# Uhr3r4_1.net
KiCad netlist of a schematic drawn in EAGLE
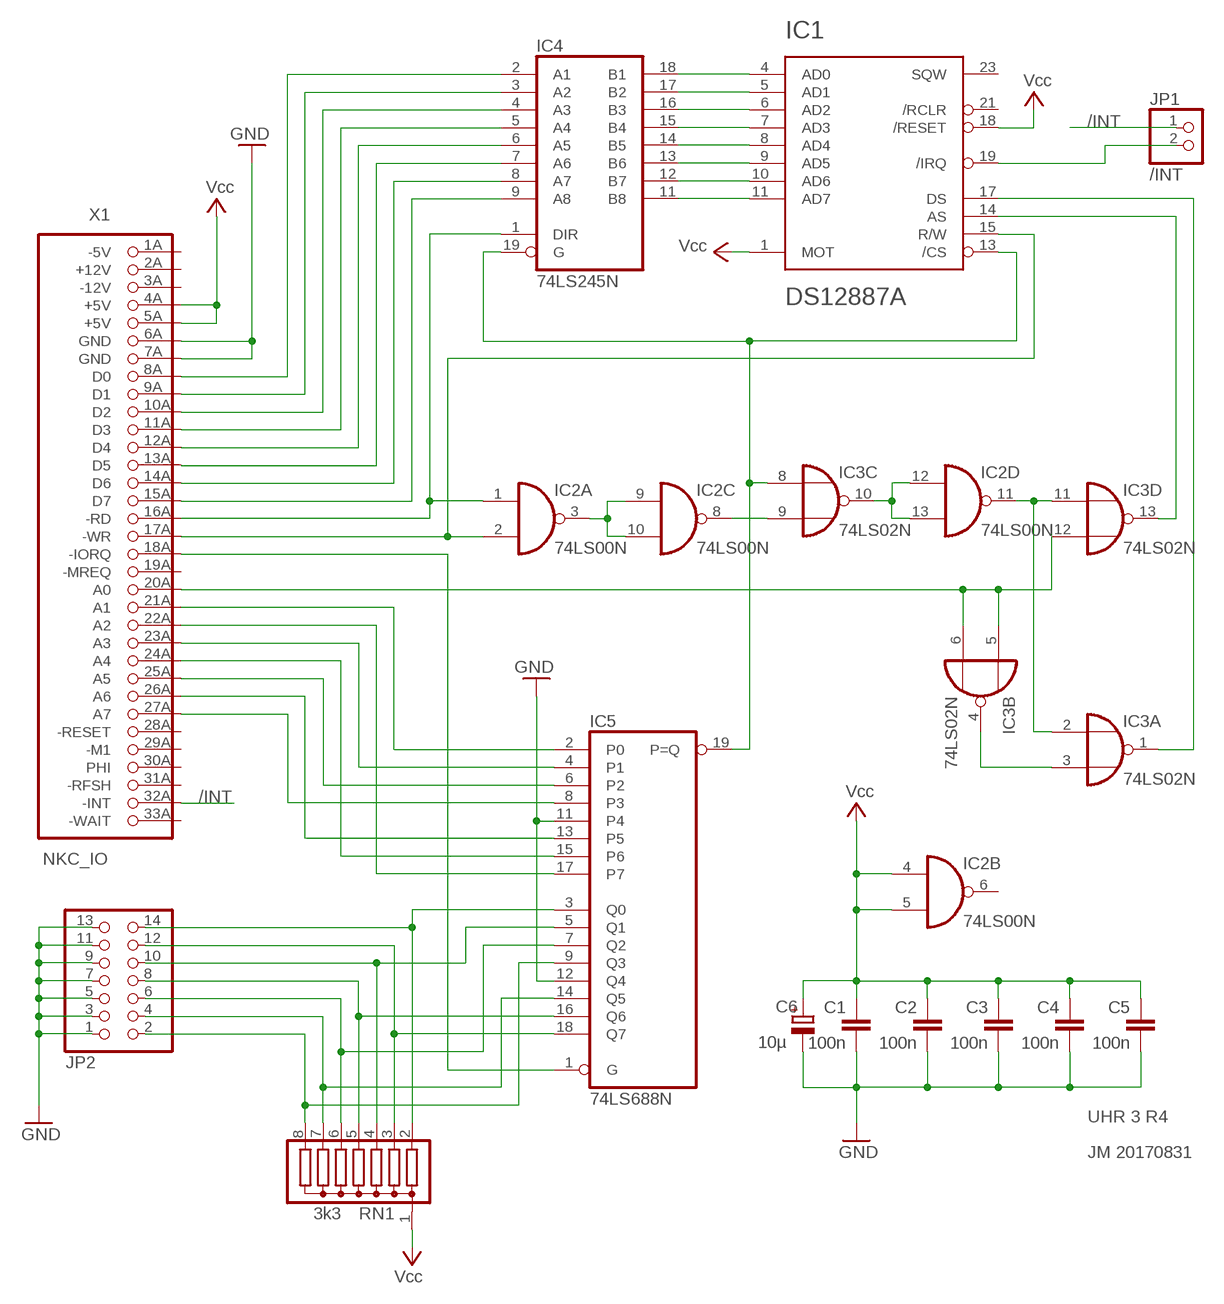
[diagram p0: schematic, sheet 1]

(export (version "E")
  (design (tool "Eeschema 10.0.6"))
  (components
    (comp (ref "C1")
      (value "100n")
      (footprint "eagle-import:C025-025X050")
      (libsource (lib "eagle-import") (part "C-EU025-025X050"))
    )
    (comp (ref "C2")
      (value "100n")
      (footprint "eagle-import:C025-025X050")
      (libsource (lib "eagle-import") (part "C-EU025-025X050"))
    )
    (comp (ref "C3")
      (value "100n")
      (footprint "eagle-import:C025-025X050")
      (libsource (lib "eagle-import") (part "C-EU025-025X050"))
    )
    (comp (ref "C4")
      (value "100n")
      (footprint "eagle-import:C025-025X050")
      (libsource (lib "eagle-import") (part "C-EU025-025X050"))
    )
    (comp (ref "C5")
      (value "100n")
      (footprint "eagle-import:C025-025X050")
      (libsource (lib "eagle-import") (part "C-EU025-025X050"))
    )
    (comp (ref "C6")
      (value "10µ")
      (footprint "eagle-import:E2,5-5")
      (libsource (lib "eagle-import") (part "CPOL-EUE2.5-5"))
    )
    (comp (ref "IC1")
      (value "DS12887A")
      (footprint "eagle-import:DIL24-6_DS")
      (libsource (lib "eagle-import") (part "DS12887A"))
    )
    (comp (ref "IC2")
      (value "74LS00N")
      (footprint "eagle-import:DIL14")
      (libsource (lib "eagle-import") (part "7400NLS"))
    )
    (comp (ref "IC3")
      (value "74LS02N")
      (footprint "eagle-import:DIL14")
      (libsource (lib "eagle-import") (part "7402NLS"))
    )
    (comp (ref "IC4")
      (value "74LS245N")
      (footprint "eagle-import:DIL20")
      (libsource (lib "eagle-import") (part "74245NLS"))
    )
    (comp (ref "IC5")
      (value "74LS688N")
      (footprint "eagle-import:DIL20")
      (libsource (lib "eagle-import") (part "74688NLS"))
    )
    (comp (ref "JP1")
      (value "/INT")
      (footprint "eagle-import:1X02")
      (libsource (lib "eagle-import") (part "PINHD-1X2"))
    )
    (comp (ref "JP2")
      (value "PINHD-2X7")
      (footprint "eagle-import:2X07")
      (libsource (lib "eagle-import") (part "PINHD-2X7"))
    )
    (comp (ref "RN1")
      (value "3k3")
      (footprint "eagle-import:SIL8")
      (libsource (lib "eagle-import") (part "G07R"))
    )
    (comp (ref "X1")
      (value "NKC_IO")
      (footprint "eagle-import:1X33_90_PCB")
      (libsource (lib "eagle-import") (part "NKC_IO"))
    )
  )
  (nets
    (net (code "1") (name "/+12V") (class "Default")
      (node (ref "X1") (pin "2A") (pinfunction "+12V_2A") (pintype "power_in"))
    )
    (net (code "2") (name "/-5V") (class "Default")
      (node (ref "X1") (pin "1A") (pinfunction "-5V_1A") (pintype "power_in"))
    )
    (net (code "3") (name "/-12V") (class "Default")
      (node (ref "X1") (pin "3A") (pinfunction "-12V_3A") (pintype "power_in"))
    )
    (net (code "4") (name "/{slash}INT") (class "Default")
      (node (ref "JP1") (pin "1") (pinfunction "1_1") (pintype "passive"))
      (node (ref "X1") (pin "32A") (pinfunction "-INT_32A") (pintype "bidirectional"))
    )
    (net (code "5") (name "GND") (class "Default")
      (node (ref "C1") (pin "1") (pinfunction "1_1") (pintype "passive"))
      (node (ref "C2") (pin "1") (pinfunction "1_1") (pintype "passive"))
      (node (ref "C3") (pin "1") (pinfunction "1_1") (pintype "passive"))
      (node (ref "C4") (pin "1") (pinfunction "1_1") (pintype "passive"))
      (node (ref "C5") (pin "1") (pinfunction "1_1") (pintype "passive"))
      (node (ref "C6") (pin "-") (pinfunction "-_-") (pintype "passive"))
      (node (ref "IC5") (pin "11") (pinfunction "P4_11") (pintype "input"))
      (node (ref "IC5") (pin "12") (pinfunction "Q4_12") (pintype "input"))
      (node (ref "JP2") (pin "1") (pinfunction "1_1") (pintype "passive"))
      (node (ref "JP2") (pin "11") (pinfunction "11_11") (pintype "passive"))
      (node (ref "JP2") (pin "13") (pinfunction "13_13") (pintype "passive"))
      (node (ref "JP2") (pin "3") (pinfunction "3_3") (pintype "passive"))
      (node (ref "JP2") (pin "5") (pinfunction "5_5") (pintype "passive"))
      (node (ref "JP2") (pin "7") (pinfunction "7_7") (pintype "passive"))
      (node (ref "JP2") (pin "9") (pinfunction "9_9") (pintype "passive"))
      (node (ref "X1") (pin "6A") (pinfunction "GND_6A") (pintype "power_in"))
      (node (ref "X1") (pin "7A") (pinfunction "GND_7A") (pintype "power_in"))
    )
    (net (code "6") (name "Net-(IC1A-AD0)") (class "Default")
      (node (ref "IC1") (pin "4") (pinfunction "AD0_4") (pintype "bidirectional"))
      (node (ref "IC4") (pin "18") (pinfunction "B1_18") (pintype "bidirectional"))
    )
    (net (code "7") (name "Net-(IC1A-AD1)") (class "Default")
      (node (ref "IC1") (pin "5") (pinfunction "AD1_5") (pintype "bidirectional"))
      (node (ref "IC4") (pin "17") (pinfunction "B2_17") (pintype "bidirectional"))
    )
    (net (code "8") (name "Net-(IC1A-AD2)") (class "Default")
      (node (ref "IC1") (pin "6") (pinfunction "AD2_6") (pintype "bidirectional"))
      (node (ref "IC4") (pin "16") (pinfunction "B3_16") (pintype "bidirectional"))
    )
    (net (code "9") (name "Net-(IC1A-AD3)") (class "Default")
      (node (ref "IC1") (pin "7") (pinfunction "AD3_7") (pintype "bidirectional"))
      (node (ref "IC4") (pin "15") (pinfunction "B4_15") (pintype "bidirectional"))
    )
    (net (code "10") (name "Net-(IC1A-AD4)") (class "Default")
      (node (ref "IC1") (pin "8") (pinfunction "AD4_8") (pintype "bidirectional"))
      (node (ref "IC4") (pin "14") (pinfunction "B5_14") (pintype "bidirectional"))
    )
    (net (code "11") (name "Net-(IC1A-AD5)") (class "Default")
      (node (ref "IC1") (pin "9") (pinfunction "AD5_9") (pintype "bidirectional"))
      (node (ref "IC4") (pin "13") (pinfunction "B6_13") (pintype "bidirectional"))
    )
    (net (code "12") (name "Net-(IC1A-AD6)") (class "Default")
      (node (ref "IC1") (pin "10") (pinfunction "AD6_10") (pintype "bidirectional"))
      (node (ref "IC4") (pin "12") (pinfunction "B7_12") (pintype "bidirectional"))
    )
    (net (code "13") (name "Net-(IC1A-AD7)") (class "Default")
      (node (ref "IC1") (pin "11") (pinfunction "AD7_11") (pintype "input"))
      (node (ref "IC4") (pin "11") (pinfunction "B8_11") (pintype "bidirectional"))
    )
    (net (code "14") (name "Net-(IC1A-AS)") (class "Default")
      (node (ref "IC1") (pin "14") (pinfunction "AS_14") (pintype "input"))
      (node (ref "IC3") (pin "13") (pinfunction "O_13") (pintype "output"))
    )
    (net (code "15") (name "Net-(IC1A-DS)") (class "Default")
      (node (ref "IC1") (pin "17") (pinfunction "DS_17") (pintype "input"))
      (node (ref "IC3") (pin "1") (pinfunction "O_1") (pintype "output"))
    )
    (net (code "16") (name "Net-(IC1A-R{slash}W)") (class "Default")
      (node (ref "IC1") (pin "15") (pinfunction "R/W_15") (pintype "input"))
      (node (ref "IC2") (pin "2") (pinfunction "I1_2") (pintype "input"))
      (node (ref "X1") (pin "17A") (pinfunction "-WR_17A") (pintype "bidirectional"))
    )
    (net (code "17") (name "Net-(IC1A-{slash}CS)") (class "Default")
      (node (ref "IC1") (pin "13") (pinfunction "/CS_13") (pintype "input"))
      (node (ref "IC3") (pin "8") (pinfunction "I0_8") (pintype "input"))
      (node (ref "IC4") (pin "19") (pinfunction "G_19") (pintype "input"))
      (node (ref "IC5") (pin "19") (pinfunction "P=Q_19") (pintype "output"))
    )
    (net (code "18") (name "Net-(IC1A-{slash}IRQ)") (class "Default")
      (node (ref "IC1") (pin "19") (pinfunction "/IRQ_19") (pintype "tri_state"))
      (node (ref "JP1") (pin "2") (pinfunction "2_2") (pintype "passive"))
    )
    (net (code "19") (name "Net-(IC2A-I0)") (class "Default")
      (node (ref "IC2") (pin "1") (pinfunction "I0_1") (pintype "input"))
      (node (ref "IC4") (pin "1") (pinfunction "DIR_1") (pintype "input"))
      (node (ref "X1") (pin "16A") (pinfunction "-RD_16A") (pintype "bidirectional"))
    )
    (net (code "20") (name "Net-(IC2A-O)") (class "Default")
      (node (ref "IC2") (pin "10") (pinfunction "I1_10") (pintype "input"))
      (node (ref "IC2") (pin "3") (pinfunction "O_3") (pintype "output"))
      (node (ref "IC2") (pin "9") (pinfunction "I0_9") (pintype "input"))
    )
    (net (code "21") (name "Net-(IC2C-O)") (class "Default")
      (node (ref "IC2") (pin "8") (pinfunction "O_8") (pintype "output"))
      (node (ref "IC3") (pin "9") (pinfunction "I1_9") (pintype "input"))
    )
    (net (code "22") (name "Net-(IC2D-I0)") (class "Default")
      (node (ref "IC2") (pin "12") (pinfunction "I0_12") (pintype "input"))
      (node (ref "IC2") (pin "13") (pinfunction "I1_13") (pintype "input"))
      (node (ref "IC3") (pin "10") (pinfunction "O_10") (pintype "output"))
    )
    (net (code "23") (name "Net-(IC2D-O)") (class "Default")
      (node (ref "IC2") (pin "11") (pinfunction "O_11") (pintype "output"))
      (node (ref "IC3") (pin "11") (pinfunction "I0_11") (pintype "input"))
      (node (ref "IC3") (pin "2") (pinfunction "I0_2") (pintype "input"))
    )
    (net (code "24") (name "Net-(IC3A-I1)") (class "Default")
      (node (ref "IC3") (pin "3") (pinfunction "I1_3") (pintype "input"))
      (node (ref "IC3") (pin "4") (pinfunction "O_4") (pintype "output"))
    )
    (net (code "25") (name "Net-(IC3B-I0)") (class "Default")
      (node (ref "IC3") (pin "12") (pinfunction "I1_12") (pintype "input"))
      (node (ref "IC3") (pin "5") (pinfunction "I0_5") (pintype "input"))
      (node (ref "IC3") (pin "6") (pinfunction "I1_6") (pintype "input"))
      (node (ref "X1") (pin "20A") (pinfunction "A0_20A") (pintype "bidirectional"))
    )
    (net (code "26") (name "Net-(IC4A-A1)") (class "Default")
      (node (ref "IC4") (pin "2") (pinfunction "A1_2") (pintype "bidirectional"))
      (node (ref "X1") (pin "8A") (pinfunction "D0_8A") (pintype "bidirectional"))
    )
    (net (code "27") (name "Net-(IC4A-A2)") (class "Default")
      (node (ref "IC4") (pin "3") (pinfunction "A2_3") (pintype "bidirectional"))
      (node (ref "X1") (pin "9A") (pinfunction "D1_9A") (pintype "bidirectional"))
    )
    (net (code "28") (name "Net-(IC4A-A3)") (class "Default")
      (node (ref "IC4") (pin "4") (pinfunction "A3_4") (pintype "bidirectional"))
      (node (ref "X1") (pin "10A") (pinfunction "D2_10A") (pintype "bidirectional"))
    )
    (net (code "29") (name "Net-(IC4A-A4)") (class "Default")
      (node (ref "IC4") (pin "5") (pinfunction "A4_5") (pintype "bidirectional"))
      (node (ref "X1") (pin "11A") (pinfunction "D3_11A") (pintype "bidirectional"))
    )
    (net (code "30") (name "Net-(IC4A-A5)") (class "Default")
      (node (ref "IC4") (pin "6") (pinfunction "A5_6") (pintype "bidirectional"))
      (node (ref "X1") (pin "12A") (pinfunction "D4_12A") (pintype "bidirectional"))
    )
    (net (code "31") (name "Net-(IC4A-A6)") (class "Default")
      (node (ref "IC4") (pin "7") (pinfunction "A6_7") (pintype "bidirectional"))
      (node (ref "X1") (pin "13A") (pinfunction "D5_13A") (pintype "bidirectional"))
    )
    (net (code "32") (name "Net-(IC4A-A7)") (class "Default")
      (node (ref "IC4") (pin "8") (pinfunction "A7_8") (pintype "bidirectional"))
      (node (ref "X1") (pin "14A") (pinfunction "D6_14A") (pintype "bidirectional"))
    )
    (net (code "33") (name "Net-(IC4A-A8)") (class "Default")
      (node (ref "IC4") (pin "9") (pinfunction "A8_9") (pintype "bidirectional"))
      (node (ref "X1") (pin "15A") (pinfunction "D7_15A") (pintype "bidirectional"))
    )
    (net (code "34") (name "Net-(IC5A-G)") (class "Default")
      (node (ref "IC5") (pin "1") (pinfunction "G_1") (pintype "input"))
      (node (ref "X1") (pin "18A") (pinfunction "-IORQ_18A") (pintype "bidirectional"))
    )
    (net (code "35") (name "Net-(IC5A-P0)") (class "Default")
      (node (ref "IC5") (pin "2") (pinfunction "P0_2") (pintype "input"))
      (node (ref "X1") (pin "21A") (pinfunction "A1_21A") (pintype "bidirectional"))
    )
    (net (code "36") (name "Net-(IC5A-P1)") (class "Default")
      (node (ref "IC5") (pin "4") (pinfunction "P1_4") (pintype "input"))
      (node (ref "X1") (pin "23A") (pinfunction "A3_23A") (pintype "bidirectional"))
    )
    (net (code "37") (name "Net-(IC5A-P2)") (class "Default")
      (node (ref "IC5") (pin "6") (pinfunction "P2_6") (pintype "input"))
      (node (ref "X1") (pin "25A") (pinfunction "A5_25A") (pintype "bidirectional"))
    )
    (net (code "38") (name "Net-(IC5A-P3)") (class "Default")
      (node (ref "IC5") (pin "8") (pinfunction "P3_8") (pintype "input"))
      (node (ref "X1") (pin "27A") (pinfunction "A7_27A") (pintype "bidirectional"))
    )
    (net (code "39") (name "Net-(IC5A-P5)") (class "Default")
      (node (ref "IC5") (pin "13") (pinfunction "P5_13") (pintype "input"))
      (node (ref "X1") (pin "26A") (pinfunction "A6_26A") (pintype "bidirectional"))
    )
    (net (code "40") (name "Net-(IC5A-P6)") (class "Default")
      (node (ref "IC5") (pin "15") (pinfunction "P6_15") (pintype "input"))
      (node (ref "X1") (pin "24A") (pinfunction "A4_24A") (pintype "bidirectional"))
    )
    (net (code "41") (name "Net-(IC5A-P7)") (class "Default")
      (node (ref "IC5") (pin "17") (pinfunction "P7_17") (pintype "input"))
      (node (ref "X1") (pin "22A") (pinfunction "A2_22A") (pintype "bidirectional"))
    )
    (net (code "42") (name "Net-(IC5A-Q0)") (class "Default")
      (node (ref "IC5") (pin "3") (pinfunction "Q0_3") (pintype "input"))
      (node (ref "JP2") (pin "14") (pinfunction "14_14") (pintype "passive"))
      (node (ref "RN1") (pin "2") (pinfunction "2_2") (pintype "passive"))
    )
    (net (code "43") (name "Net-(IC5A-Q1)") (class "Default")
      (node (ref "IC5") (pin "5") (pinfunction "Q1_5") (pintype "input"))
      (node (ref "JP2") (pin "10") (pinfunction "10_10") (pintype "passive"))
      (node (ref "RN1") (pin "4") (pinfunction "4_4") (pintype "passive"))
    )
    (net (code "44") (name "Net-(IC5A-Q2)") (class "Default")
      (node (ref "IC5") (pin "7") (pinfunction "Q2_7") (pintype "input"))
      (node (ref "JP2") (pin "6") (pinfunction "6_6") (pintype "passive"))
      (node (ref "RN1") (pin "6") (pinfunction "6_6") (pintype "passive"))
    )
    (net (code "45") (name "Net-(IC5A-Q3)") (class "Default")
      (node (ref "IC5") (pin "9") (pinfunction "Q3_9") (pintype "input"))
      (node (ref "JP2") (pin "2") (pinfunction "2_2") (pintype "passive"))
      (node (ref "RN1") (pin "8") (pinfunction "8_8") (pintype "passive"))
    )
    (net (code "46") (name "Net-(IC5A-Q5)") (class "Default")
      (node (ref "IC5") (pin "14") (pinfunction "Q5_14") (pintype "input"))
      (node (ref "JP2") (pin "4") (pinfunction "4_4") (pintype "passive"))
      (node (ref "RN1") (pin "7") (pinfunction "7_7") (pintype "passive"))
    )
    (net (code "47") (name "Net-(IC5A-Q6)") (class "Default")
      (node (ref "IC5") (pin "16") (pinfunction "Q6_16") (pintype "input"))
      (node (ref "JP2") (pin "8") (pinfunction "8_8") (pintype "passive"))
      (node (ref "RN1") (pin "5") (pinfunction "5_5") (pintype "passive"))
    )
    (net (code "48") (name "Net-(IC5A-Q7)") (class "Default")
      (node (ref "IC5") (pin "18") (pinfunction "Q7_18") (pintype "input"))
      (node (ref "JP2") (pin "12") (pinfunction "12_12") (pintype "passive"))
      (node (ref "RN1") (pin "3") (pinfunction "3_3") (pintype "passive"))
    )
    (net (code "49") (name "Vcc") (class "Default")
      (node (ref "C1") (pin "2") (pinfunction "2_2") (pintype "passive"))
      (node (ref "C2") (pin "2") (pinfunction "2_2") (pintype "passive"))
      (node (ref "C3") (pin "2") (pinfunction "2_2") (pintype "passive"))
      (node (ref "C4") (pin "2") (pinfunction "2_2") (pintype "passive"))
      (node (ref "C5") (pin "2") (pinfunction "2_2") (pintype "passive"))
      (node (ref "C6") (pin "+") (pinfunction "+_+") (pintype "passive"))
      (node (ref "IC1") (pin "1") (pinfunction "MOT_1") (pintype "input"))
      (node (ref "IC1") (pin "18") (pinfunction "/RESET_18") (pintype "input"))
      (node (ref "IC2") (pin "4") (pinfunction "I0_4") (pintype "input"))
      (node (ref "IC2") (pin "5") (pinfunction "I1_5") (pintype "input"))
      (node (ref "RN1") (pin "1") (pinfunction "1_1") (pintype "passive"))
      (node (ref "X1") (pin "4A") (pinfunction "+5V_4A") (pintype "power_in"))
      (node (ref "X1") (pin "5A") (pinfunction "+5V_5A") (pintype "power_in"))
    )
    (net (code "50") (name "unconnected-(IC1A-SQW-Pad23)") (class "Default")
      (node (ref "IC1") (pin "23") (pinfunction "SQW_23") (pintype "output"))
    )
    (net (code "51") (name "unconnected-(IC1A-{slash}RCLR-Pad21)") (class "Default")
      (node (ref "IC1") (pin "21") (pinfunction "/RCLR_21") (pintype "input"))
    )
    (net (code "52") (name "unconnected-(IC2B-O-Pad6)") (class "Default")
      (node (ref "IC2") (pin "6") (pinfunction "O_6") (pintype "output"))
    )
    (net (code "53") (name "unconnected-(X1--M1-Pad29A)") (class "Default")
      (node (ref "X1") (pin "29A") (pinfunction "-M1_29A") (pintype "bidirectional"))
    )
    (net (code "54") (name "unconnected-(X1--MREQ-Pad19A)") (class "Default")
      (node (ref "X1") (pin "19A") (pinfunction "-MREQ_19A") (pintype "bidirectional"))
    )
    (net (code "55") (name "unconnected-(X1--RESET-Pad28A)") (class "Default")
      (node (ref "X1") (pin "28A") (pinfunction "-RESET_28A") (pintype "bidirectional"))
    )
    (net (code "56") (name "unconnected-(X1--RFSH-Pad31A)") (class "Default")
      (node (ref "X1") (pin "31A") (pinfunction "-RFSH_31A") (pintype "bidirectional"))
    )
    (net (code "57") (name "unconnected-(X1--WAIT-Pad33A)") (class "Default")
      (node (ref "X1") (pin "33A") (pinfunction "-WAIT_33A") (pintype "bidirectional"))
    )
    (net (code "58") (name "unconnected-(X1-PHI-Pad30A)") (class "Default")
      (node (ref "X1") (pin "30A") (pinfunction "PHI_30A") (pintype "bidirectional"))
    )
  )
)
